# ESP07_CarSentry.net
KiCad netlist of a schematic drawn in EAGLE
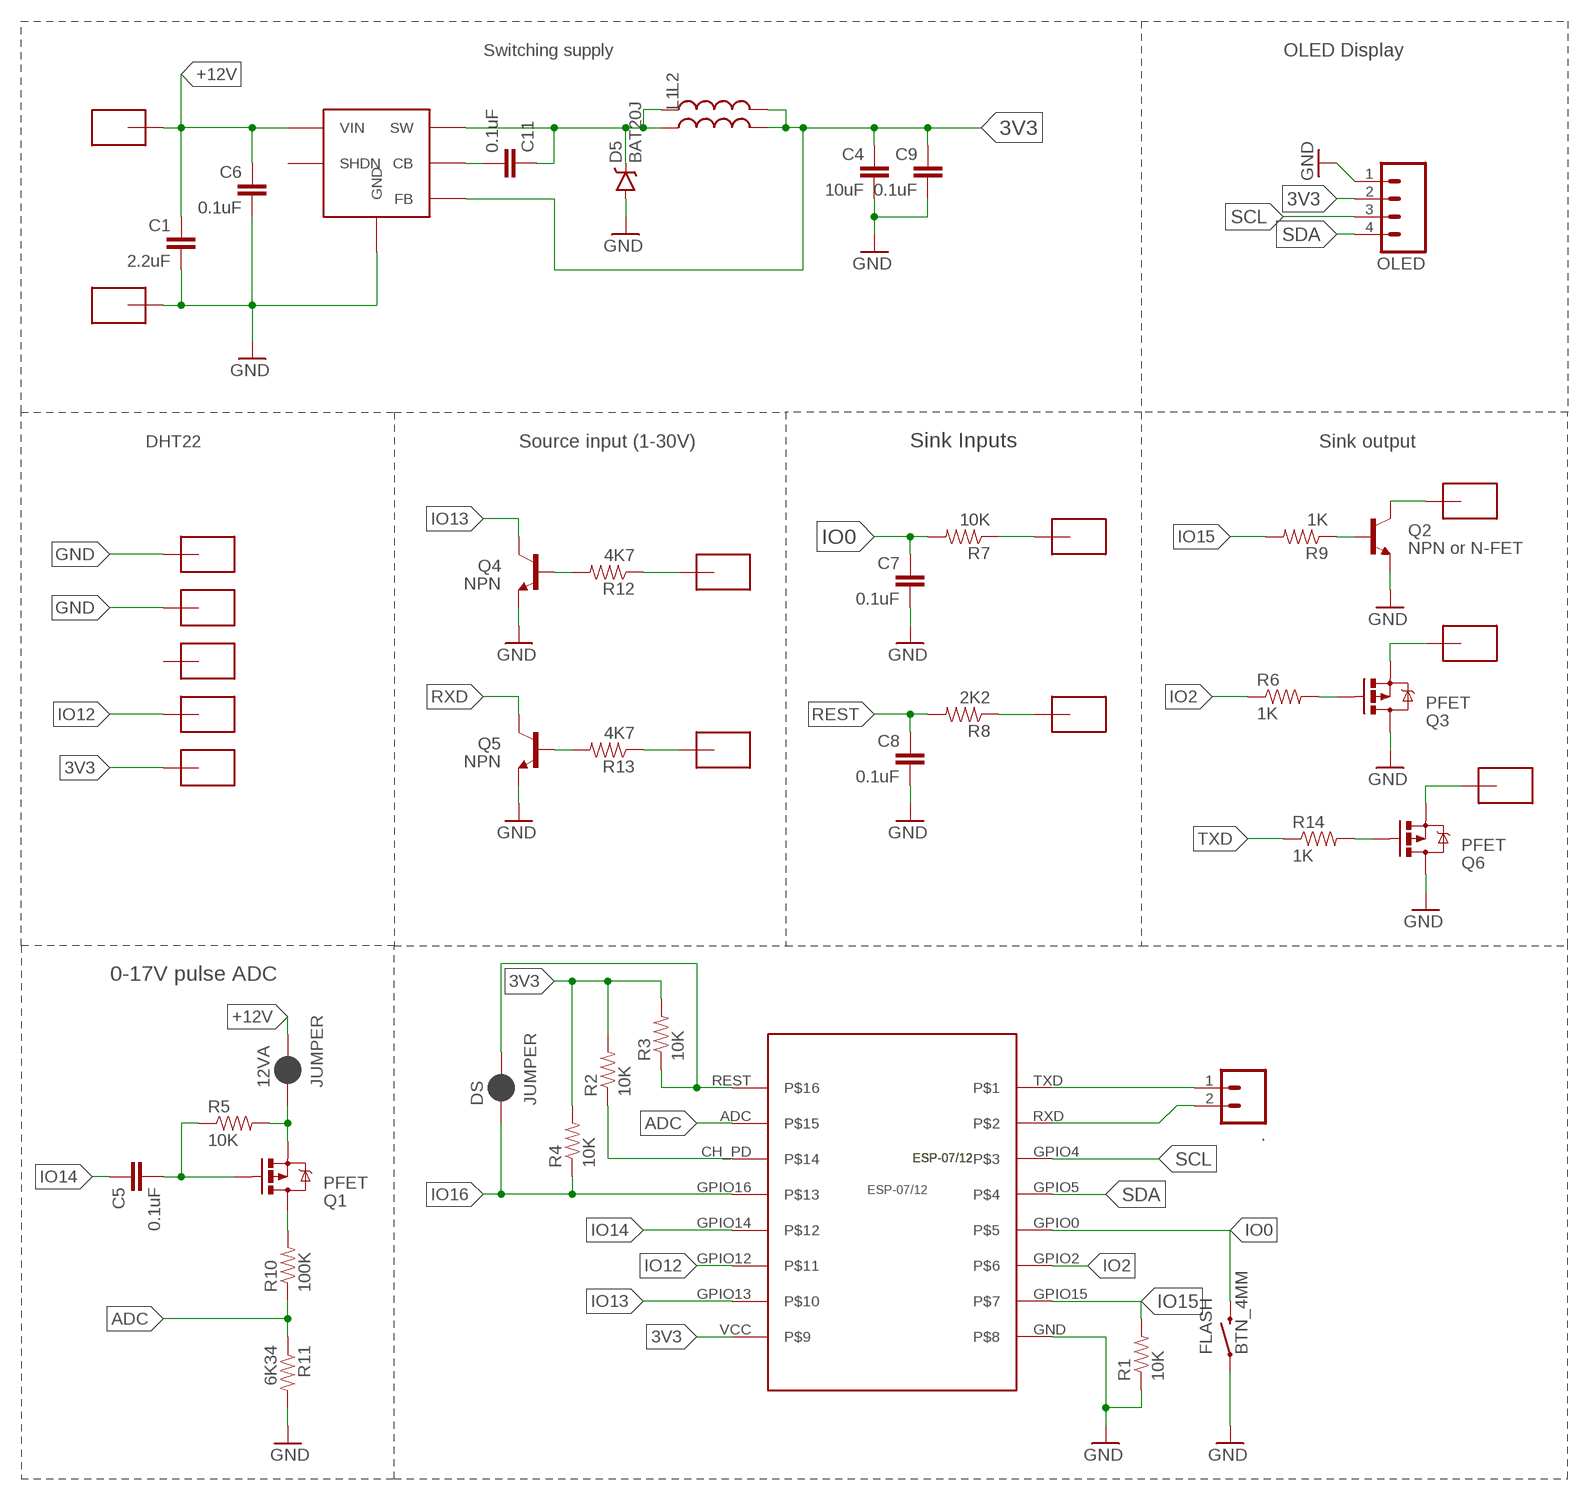
[diagram p0: schematic, sheet 1]

(export (version "E")
  (design (tool "Eeschema 10.0.6"))
  (components
    (comp (ref ".")
      (value "M02PTH")
      (footprint "eagle-import:1X02")
      (libsource (lib "eagle-import") (part "M02PTH"))
    )
    (comp (ref "12VA")
      (value "JUMPER")
      (footprint "eagle-import:PAD-JUMPER-2-NC_BY_PASTE_YES_SILK")
      (libsource (lib "eagle-import") (part "JUMPER-PAD-2-NC_BY_PASTE"))
    )
    (comp (ref "C1")
      (value "2.2uF")
      (footprint "eagle-import:0805-CAP")
      (libsource (lib "eagle-import") (part "CAP"))
    )
    (comp (ref "C4")
      (value "10uF")
      (footprint "eagle-import:0805-CAP")
      (libsource (lib "eagle-import") (part "CAP"))
    )
    (comp (ref "C5")
      (value "0.1uF")
      (footprint "eagle-import:0805-CAP")
      (libsource (lib "eagle-import") (part "CAP"))
    )
    (comp (ref "C6")
      (value "0.1uF")
      (footprint "eagle-import:0805-CAP")
      (libsource (lib "eagle-import") (part "CAP"))
    )
    (comp (ref "C7")
      (value "0.1uF")
      (footprint "eagle-import:0805-CAP")
      (libsource (lib "eagle-import") (part "CAP"))
    )
    (comp (ref "C8")
      (value "0.1uF")
      (footprint "eagle-import:0805-CAP")
      (libsource (lib "eagle-import") (part "CAP"))
    )
    (comp (ref "C9")
      (value "0.1uF")
      (footprint "eagle-import:0805-CAP")
      (libsource (lib "eagle-import") (part "CAP"))
    )
    (comp (ref "C11")
      (value "0.1uF")
      (footprint "eagle-import:0805-CAP")
      (libsource (lib "eagle-import") (part "CAP"))
    )
    (comp (ref "D5")
      (value "BAT20J")
      (footprint "eagle-import:SOD-323")
      (libsource (lib "eagle-import") (part "DIODE-SCHOTTKY-BAT20J"))
    )
    (comp (ref "DS")
      (value "JUMPER")
      (footprint "eagle-import:PAD-JUMPER-2-NC_BY_PASTE_YES_SILK")
      (libsource (lib "eagle-import") (part "JUMPER-PAD-2-NC_BY_PASTE"))
    )
    (comp (ref "FLASH")
      (value "BTN_4MM")
      (footprint "eagle-import:BTN_4MM")
      (libsource (lib "eagle-import") (part "BTN_4MM"))
    )
    (comp (ref "L1")
      (value "INDUCTOR0805")
      (footprint "eagle-import:0805")
      (libsource (lib "eagle-import") (part "INDUCTOR0805"))
    )
    (comp (ref "L2")
      (value "INDUCTOR0805")
      (footprint "eagle-import:0805")
      (libsource (lib "eagle-import") (part "INDUCTOR0805"))
    )
    (comp (ref "OLED")
      (value "M04LOCK")
      (footprint "eagle-import:1X04_LOCK")
      (libsource (lib "eagle-import") (part "M04LOCK"))
    )
    (comp (ref "Q1")
      (value "PFET")
      (footprint "eagle-import:SOT23-3")
      (libsource (lib "eagle-import") (part "MOSFET-PCHANNEL"))
    )
    (comp (ref "Q2")
      (value "NPN or N-FET")
      (footprint "eagle-import:SOT23-3")
      (libsource (lib "eagle-import") (part "TRANSISTOR_NPNSOT23-3"))
    )
    (comp (ref "Q3")
      (value "PFET")
      (footprint "eagle-import:SOT23-3")
      (libsource (lib "eagle-import") (part "MOSFET-PCHANNEL"))
    )
    (comp (ref "Q4")
      (value "NPN")
      (footprint "eagle-import:SOT23-3")
      (libsource (lib "eagle-import") (part "TRANSISTOR_NPNSOT23-3"))
    )
    (comp (ref "Q5")
      (value "NPN")
      (footprint "eagle-import:SOT23-3")
      (libsource (lib "eagle-import") (part "TRANSISTOR_NPNSOT23-3"))
    )
    (comp (ref "Q6")
      (value "PFET")
      (footprint "eagle-import:SOT23-3")
      (libsource (lib "eagle-import") (part "MOSFET-PCHANNEL"))
    )
    (comp (ref "R1")
      (value "10K")
      (footprint "eagle-import:0805")
      (libsource (lib "eagle-import") (part "RESISTOR0805-RES"))
    )
    (comp (ref "R2")
      (value "10K")
      (footprint "eagle-import:0805")
      (libsource (lib "eagle-import") (part "RESISTOR0805-RES"))
    )
    (comp (ref "R3")
      (value "10K")
      (footprint "eagle-import:0805")
      (libsource (lib "eagle-import") (part "RESISTOR0805-RES"))
    )
    (comp (ref "R4")
      (value "10K")
      (footprint "eagle-import:0805")
      (libsource (lib "eagle-import") (part "RESISTOR0805-RES"))
    )
    (comp (ref "R5")
      (value "10K")
      (footprint "eagle-import:0805")
      (libsource (lib "eagle-import") (part "RESISTOR0805-RES"))
    )
    (comp (ref "R6")
      (value "1K")
      (footprint "eagle-import:0805")
      (libsource (lib "eagle-import") (part "RESISTOR0805-RES"))
    )
    (comp (ref "R7")
      (value "10K")
      (footprint "eagle-import:0805")
      (libsource (lib "eagle-import") (part "RESISTOR0805-RES"))
    )
    (comp (ref "R8")
      (value "2K2")
      (footprint "eagle-import:0805")
      (libsource (lib "eagle-import") (part "RESISTOR0805-RES"))
    )
    (comp (ref "R9")
      (value "1K")
      (footprint "eagle-import:0805")
      (libsource (lib "eagle-import") (part "RESISTOR0805-RES"))
    )
    (comp (ref "R10")
      (value "100K")
      (footprint "eagle-import:0805")
      (libsource (lib "eagle-import") (part "RESISTOR0805-RES"))
    )
    (comp (ref "R11")
      (value "6K34")
      (footprint "eagle-import:0805")
      (libsource (lib "eagle-import") (part "RESISTOR0805-RES"))
    )
    (comp (ref "R12")
      (value "4K7")
      (footprint "eagle-import:0805")
      (libsource (lib "eagle-import") (part "RESISTOR0805-RES"))
    )
    (comp (ref "R13")
      (value "4K7")
      (footprint "eagle-import:0805")
      (libsource (lib "eagle-import") (part "RESISTOR0805-RES"))
    )
    (comp (ref "R14")
      (value "1K")
      (footprint "eagle-import:0805")
      (libsource (lib "eagle-import") (part "RESISTOR0805-RES"))
    )
    (comp (ref "U$1")
      (value "ESP-07/12")
      (footprint "eagle-import:ESP-07_12")
      (libsource (lib "eagle-import") (part "ESP-07/12"))
    )
    (comp (ref "U$2")
      (value "SMD-PAD1")
      (footprint "eagle-import:SMD-PAD1")
      (libsource (lib "eagle-import") (part "SMD-PAD1"))
    )
    (comp (ref "U$3")
      (value "SMD-PAD1")
      (footprint "eagle-import:SMD-PAD1")
      (libsource (lib "eagle-import") (part "SMD-PAD1"))
    )
    (comp (ref "U$4")
      (value "SMD-PAD1")
      (footprint "eagle-import:SMD-PAD1")
      (libsource (lib "eagle-import") (part "SMD-PAD1"))
    )
    (comp (ref "U$5")
      (value "SMD-PAD1")
      (footprint "eagle-import:SMD-PAD1")
      (libsource (lib "eagle-import") (part "SMD-PAD1"))
    )
    (comp (ref "U$6")
      (value "SMD-PAD1")
      (footprint "eagle-import:SMD-PAD1")
      (libsource (lib "eagle-import") (part "SMD-PAD1"))
    )
    (comp (ref "U$7")
      (value "SMD-PAD1")
      (footprint "eagle-import:SMD-PAD1")
      (libsource (lib "eagle-import") (part "SMD-PAD1"))
    )
    (comp (ref "U$8")
      (value "SMD-PAD1")
      (footprint "eagle-import:SMD-PAD1")
      (libsource (lib "eagle-import") (part "SMD-PAD1"))
    )
    (comp (ref "U$9")
      (value "SMD-PAD1")
      (footprint "eagle-import:SMD-PAD1")
      (libsource (lib "eagle-import") (part "SMD-PAD1"))
    )
    (comp (ref "U$10")
      (value "SMD-PAD1")
      (footprint "eagle-import:SMD-PAD1")
      (libsource (lib "eagle-import") (part "SMD-PAD1"))
    )
    (comp (ref "U$11")
      (value "SMD-PAD1")
      (footprint "eagle-import:SMD-PAD1")
      (libsource (lib "eagle-import") (part "SMD-PAD1"))
    )
    (comp (ref "U$12")
      (value "SMD-PAD1")
      (footprint "eagle-import:SMD-PAD1")
      (libsource (lib "eagle-import") (part "SMD-PAD1"))
    )
    (comp (ref "U$13")
      (value "SMD-PAD1")
      (footprint "eagle-import:SMD-PAD1")
      (libsource (lib "eagle-import") (part "SMD-PAD1"))
    )
    (comp (ref "U$14")
      (value "SMD-PAD1")
      (footprint "eagle-import:SMD-PAD1")
      (libsource (lib "eagle-import") (part "SMD-PAD1"))
    )
    (comp (ref "U$16")
      (value "SMD-PAD1")
      (footprint "eagle-import:SMD-PAD1")
      (libsource (lib "eagle-import") (part "SMD-PAD1"))
    )
    (comp (ref "VREG1")
      (value "LMR16006YQ3DDCRQ1")
      (footprint "eagle-import:SOT-23-6")
      (libsource (lib "eagle-import") (part "LMR16006YQ"))
    )
  )
  (nets
    (net (code "1") (name "+12V") (class "Default")
      (node (ref "12VA") (pin "2") (pinfunction "2_2") (pintype "passive"))
      (node (ref "C1") (pin "1") (pinfunction "1_1") (pintype "passive"))
      (node (ref "C6") (pin "1") (pinfunction "1_1") (pintype "passive"))
      (node (ref "U$16") (pin ">NAME") (pinfunction "P$1_>NAME") (pintype "bidirectional"))
      (node (ref "VREG1") (pin "5") (pinfunction "VIN_5") (pintype "input"))
    )
    (net (code "2") (name "3V3") (class "Default")
      (node (ref "C4") (pin "1") (pinfunction "1_1") (pintype "passive"))
      (node (ref "C9") (pin "1") (pinfunction "1_1") (pintype "passive"))
      (node (ref "L1") (pin "2") (pinfunction "2_2") (pintype "passive"))
      (node (ref "L2") (pin "2") (pinfunction "2_2") (pintype "passive"))
      (node (ref "OLED") (pin "2") (pinfunction "2_2") (pintype "passive"))
      (node (ref "R2") (pin "2") (pinfunction "2_2") (pintype "passive"))
      (node (ref "R3") (pin "2") (pinfunction "2_2") (pintype "passive"))
      (node (ref "R4") (pin "2") (pinfunction "2_2") (pintype "passive"))
      (node (ref "U$1") (pin "VCC") (pinfunction "P$9_VCC") (pintype "bidirectional"))
      (node (ref "U$4") (pin ">NAME") (pinfunction "P$1_>NAME") (pintype "bidirectional"))
      (node (ref "VREG1") (pin "3") (pinfunction "FB_3") (pintype "input"))
    )
    (net (code "3") (name "ADC") (class "Default")
      (node (ref "R10") (pin "1") (pinfunction "1_1") (pintype "passive"))
      (node (ref "R11") (pin "1") (pinfunction "1_1") (pintype "passive"))
      (node (ref "U$1") (pin "ADC") (pinfunction "P$15_ADC") (pintype "bidirectional"))
    )
    (net (code "4") (name "GND") (class "Default")
      (node (ref "C1") (pin "2") (pinfunction "2_2") (pintype "passive"))
      (node (ref "C4") (pin "2") (pinfunction "2_2") (pintype "passive"))
      (node (ref "C6") (pin "2") (pinfunction "2_2") (pintype "passive"))
      (node (ref "C7") (pin "2") (pinfunction "2_2") (pintype "passive"))
      (node (ref "C8") (pin "2") (pinfunction "2_2") (pintype "passive"))
      (node (ref "C9") (pin "2") (pinfunction "2_2") (pintype "passive"))
      (node (ref "D5") (pin "A") (pinfunction "A_A") (pintype "passive"))
      (node (ref "FLASH") (pin "1") (pinfunction "1_1") (pintype "passive"))
      (node (ref "OLED") (pin "1") (pinfunction "1_1") (pintype "passive"))
      (node (ref "Q2") (pin "2") (pinfunction "E_2") (pintype "passive"))
      (node (ref "Q3") (pin "3") (pinfunction "D_3") (pintype "passive"))
      (node (ref "Q4") (pin "2") (pinfunction "E_2") (pintype "passive"))
      (node (ref "Q5") (pin "2") (pinfunction "E_2") (pintype "passive"))
      (node (ref "Q6") (pin "3") (pinfunction "D_3") (pintype "passive"))
      (node (ref "R1") (pin "1") (pinfunction "1_1") (pintype "passive"))
      (node (ref "R11") (pin "2") (pinfunction "2_2") (pintype "passive"))
      (node (ref "U$1") (pin "GND") (pinfunction "P$8_GND") (pintype "bidirectional"))
      (node (ref "U$11") (pin ">NAME") (pinfunction "P$1_>NAME") (pintype "bidirectional"))
      (node (ref "U$6") (pin ">NAME") (pinfunction "P$1_>NAME") (pintype "bidirectional"))
      (node (ref "U$8") (pin ">NAME") (pinfunction "P$1_>NAME") (pintype "bidirectional"))
      (node (ref "VREG1") (pin "2") (pinfunction "GND_2") (pintype "input"))
    )
    (net (code "5") (name "IO0") (class "Default")
      (node (ref "C7") (pin "1") (pinfunction "1_1") (pintype "passive"))
      (node (ref "FLASH") (pin "2") (pinfunction "2_2") (pintype "passive"))
      (node (ref "R7") (pin "2") (pinfunction "2_2") (pintype "passive"))
      (node (ref "U$1") (pin "GPIO0") (pinfunction "P$5_GPIO0") (pintype "bidirectional"))
    )
    (net (code "6") (name "IO2") (class "Default")
      (node (ref "R6") (pin "1") (pinfunction "1_1") (pintype "passive"))
      (node (ref "U$1") (pin "GPIO2") (pinfunction "P$6_GPIO2") (pintype "bidirectional"))
    )
    (net (code "7") (name "IO12") (class "Default")
      (node (ref "U$1") (pin "GPIO12") (pinfunction "P$11_GPIO12") (pintype "bidirectional"))
      (node (ref "U$5") (pin ">NAME") (pinfunction "P$1_>NAME") (pintype "bidirectional"))
    )
    (net (code "8") (name "IO13") (class "Default")
      (node (ref "Q4") (pin "3") (pinfunction "C_3") (pintype "passive"))
      (node (ref "U$1") (pin "GPIO13") (pinfunction "P$10_GPIO13") (pintype "bidirectional"))
    )
    (net (code "9") (name "IO14") (class "Default")
      (node (ref "C5") (pin "1") (pinfunction "1_1") (pintype "passive"))
      (node (ref "U$1") (pin "GPIO14") (pinfunction "P$12_GPIO14") (pintype "bidirectional"))
    )
    (net (code "10") (name "IO15") (class "Default")
      (node (ref "R1") (pin "2") (pinfunction "2_2") (pintype "passive"))
      (node (ref "R9") (pin "2") (pinfunction "2_2") (pintype "passive"))
      (node (ref "U$1") (pin "GPIO15") (pinfunction "P$7_GPIO15") (pintype "bidirectional"))
    )
    (net (code "11") (name "IO16") (class "Default")
      (node (ref "DS") (pin "1") (pinfunction "1_1") (pintype "passive"))
      (node (ref "R4") (pin "1") (pinfunction "1_1") (pintype "passive"))
      (node (ref "U$1") (pin "GPIO16") (pinfunction "P$13_GPIO16") (pintype "bidirectional"))
    )
    (net (code "12") (name "Net-(Q1-D)") (class "Default")
      (node (ref "Q1") (pin "3") (pinfunction "D_3") (pintype "passive"))
      (node (ref "R10") (pin "2") (pinfunction "2_2") (pintype "passive"))
    )
    (net (code "13") (name "Net-(Q1-G)") (class "Default")
      (node (ref "C5") (pin "2") (pinfunction "2_2") (pintype "passive"))
      (node (ref "Q1") (pin "1") (pinfunction "G_1") (pintype "passive"))
      (node (ref "R5") (pin "1") (pinfunction "1_1") (pintype "passive"))
    )
    (net (code "14") (name "Net-(Q1-S)") (class "Default")
      (node (ref "12VA") (pin "1") (pinfunction "1_1") (pintype "passive"))
      (node (ref "Q1") (pin "2") (pinfunction "S_2") (pintype "passive"))
      (node (ref "R5") (pin "2") (pinfunction "2_2") (pintype "passive"))
    )
    (net (code "15") (name "Net-(Q2-B)") (class "Default")
      (node (ref "Q2") (pin "1") (pinfunction "B_1") (pintype "passive"))
      (node (ref "R9") (pin "1") (pinfunction "1_1") (pintype "passive"))
    )
    (net (code "16") (name "Net-(Q2-C)") (class "Default")
      (node (ref "Q2") (pin "3") (pinfunction "C_3") (pintype "passive"))
      (node (ref "U$3") (pin ">NAME") (pinfunction "P$1_>NAME") (pintype "bidirectional"))
    )
    (net (code "17") (name "Net-(Q3-G)") (class "Default")
      (node (ref "Q3") (pin "1") (pinfunction "G_1") (pintype "passive"))
      (node (ref "R6") (pin "2") (pinfunction "2_2") (pintype "passive"))
    )
    (net (code "18") (name "Net-(Q3-S)") (class "Default")
      (node (ref "Q3") (pin "2") (pinfunction "S_2") (pintype "passive"))
      (node (ref "U$9") (pin ">NAME") (pinfunction "P$1_>NAME") (pintype "bidirectional"))
    )
    (net (code "19") (name "Net-(Q4-B)") (class "Default")
      (node (ref "Q4") (pin "1") (pinfunction "B_1") (pintype "passive"))
      (node (ref "R12") (pin "2") (pinfunction "2_2") (pintype "passive"))
    )
    (net (code "20") (name "Net-(Q5-B)") (class "Default")
      (node (ref "Q5") (pin "1") (pinfunction "B_1") (pintype "passive"))
      (node (ref "R13") (pin "2") (pinfunction "2_2") (pintype "passive"))
    )
    (net (code "21") (name "Net-(Q6-G)") (class "Default")
      (node (ref "Q6") (pin "1") (pinfunction "G_1") (pintype "passive"))
      (node (ref "R14") (pin "2") (pinfunction "2_2") (pintype "passive"))
    )
    (net (code "22") (name "Net-(Q6-S)") (class "Default")
      (node (ref "Q6") (pin "2") (pinfunction "S_2") (pintype "passive"))
      (node (ref "U$13") (pin ">NAME") (pinfunction "P$1_>NAME") (pintype "bidirectional"))
    )
    (net (code "23") (name "Net-(U$1-P$14)") (class "Default")
      (node (ref "R2") (pin "1") (pinfunction "1_1") (pintype "passive"))
      (node (ref "U$1") (pin "CH_PD") (pinfunction "P$14_CH_PD") (pintype "bidirectional"))
    )
    (net (code "24") (name "Net-(U$2-P$1)") (class "Default")
      (node (ref "R12") (pin "1") (pinfunction "1_1") (pintype "passive"))
      (node (ref "U$2") (pin ">NAME") (pinfunction "P$1_>NAME") (pintype "bidirectional"))
    )
    (net (code "25") (name "Net-(U$10-P$1)") (class "Default")
      (node (ref "R13") (pin "1") (pinfunction "1_1") (pintype "passive"))
      (node (ref "U$10") (pin ">NAME") (pinfunction "P$1_>NAME") (pintype "bidirectional"))
    )
    (net (code "26") (name "Net-(U$12-P$1)") (class "Default")
      (node (ref "R8") (pin "1") (pinfunction "1_1") (pintype "passive"))
      (node (ref "U$12") (pin ">NAME") (pinfunction "P$1_>NAME") (pintype "bidirectional"))
    )
    (net (code "27") (name "Net-(U$14-P$1)") (class "Default")
      (node (ref "R7") (pin "1") (pinfunction "1_1") (pintype "passive"))
      (node (ref "U$14") (pin ">NAME") (pinfunction "P$1_>NAME") (pintype "bidirectional"))
    )
    (net (code "28") (name "Net-(VREG1-CB)") (class "Default")
      (node (ref "C11") (pin "2") (pinfunction "2_2") (pintype "passive"))
      (node (ref "VREG1") (pin "1") (pinfunction "CB_1") (pintype "input"))
    )
    (net (code "29") (name "Net-(VREG1-SW)") (class "Default")
      (node (ref "C11") (pin "1") (pinfunction "1_1") (pintype "passive"))
      (node (ref "D5") (pin "C") (pinfunction "C_C") (pintype "passive"))
      (node (ref "L1") (pin "1") (pinfunction "1_1") (pintype "passive"))
      (node (ref "L2") (pin "1") (pinfunction "1_1") (pintype "passive"))
      (node (ref "VREG1") (pin "6") (pinfunction "SW_6") (pintype "output"))
    )
    (net (code "30") (name "REST") (class "Default")
      (node (ref "C8") (pin "1") (pinfunction "1_1") (pintype "passive"))
      (node (ref "DS") (pin "2") (pinfunction "2_2") (pintype "passive"))
      (node (ref "R3") (pin "1") (pinfunction "1_1") (pintype "passive"))
      (node (ref "R8") (pin "2") (pinfunction "2_2") (pintype "passive"))
      (node (ref "U$1") (pin "REST") (pinfunction "P$16_REST") (pintype "bidirectional"))
    )
    (net (code "31") (name "RXD") (class "Default")
      (node (ref ".") (pin "2") (pinfunction "2_2") (pintype "passive"))
      (node (ref "Q5") (pin "3") (pinfunction "C_3") (pintype "passive"))
      (node (ref "U$1") (pin "RXD") (pinfunction "P$2_RXD") (pintype "bidirectional"))
    )
    (net (code "32") (name "SCL") (class "Default")
      (node (ref "OLED") (pin "3") (pinfunction "3_3") (pintype "passive"))
      (node (ref "U$1") (pin "GPIO4") (pinfunction "P$3_GPIO4") (pintype "bidirectional"))
    )
    (net (code "33") (name "SDA") (class "Default")
      (node (ref "OLED") (pin "4") (pinfunction "4_4") (pintype "passive"))
      (node (ref "U$1") (pin "GPIO5") (pinfunction "P$4_GPIO5") (pintype "bidirectional"))
    )
    (net (code "34") (name "TXD") (class "Default")
      (node (ref ".") (pin "1") (pinfunction "1_1") (pintype "passive"))
      (node (ref "R14") (pin "1") (pinfunction "1_1") (pintype "passive"))
      (node (ref "U$1") (pin "TXD") (pinfunction "P$1_TXD") (pintype "bidirectional"))
    )
    (net (code "35") (name "unconnected-(U$7-P$1-Pad>NAME)") (class "Default")
      (node (ref "U$7") (pin ">NAME") (pinfunction "P$1_>NAME") (pintype "bidirectional"))
    )
    (net (code "36") (name "unconnected-(VREG1-SHDN-Pad4)") (class "Default")
      (node (ref "VREG1") (pin "4") (pinfunction "SHDN_4") (pintype "input"))
    )
  )
)
